# schematic1.net
KiCad netlist of a schematic drawn in EAGLE
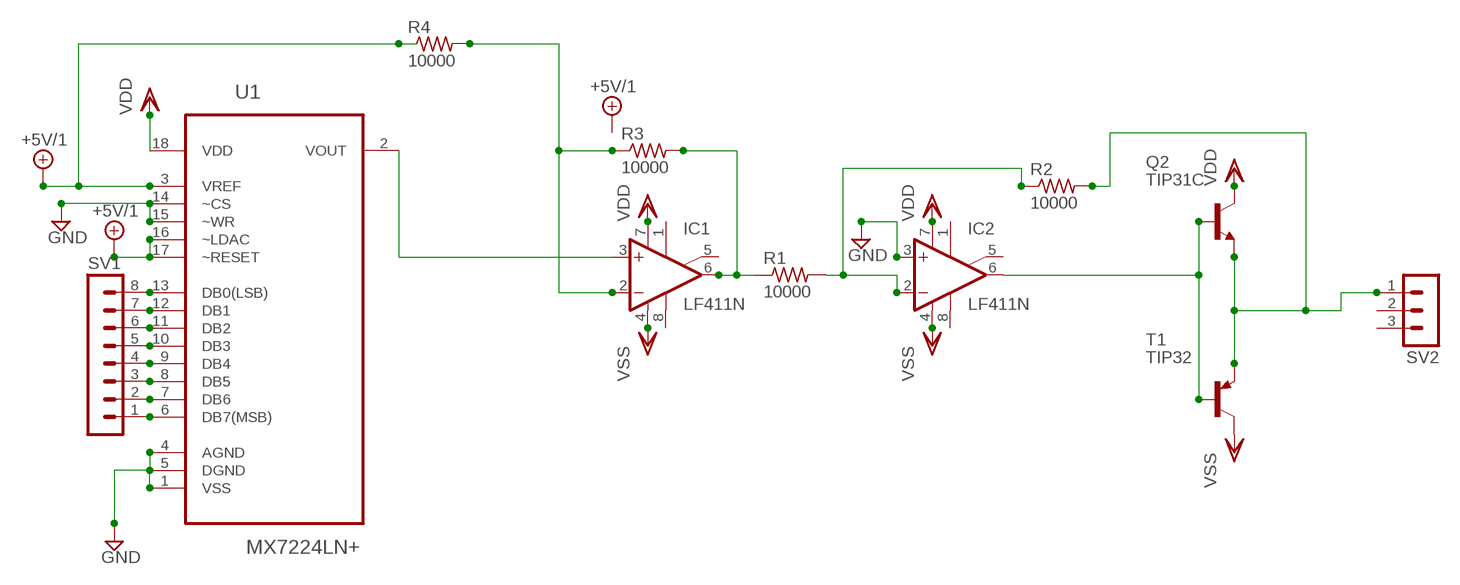
[diagram p0: schematic, sheet 1]

(export (version "E")
  (design (tool "Eeschema 10.0.6"))
  (components
    (comp (ref "IC1")
      (value "LF411N")
      (footprint "eagle-import:DIL08")
      (libsource (lib "eagle-import") (part "LF411N"))
    )
    (comp (ref "IC2")
      (value "LF411N")
      (footprint "eagle-import:DIL08")
      (libsource (lib "eagle-import") (part "LF411N"))
    )
    (comp (ref "Q2")
      (value "TIP31C")
      (footprint "eagle-import:TO220")
      (libsource (lib "eagle-import") (part "TIP31C"))
    )
    (comp (ref "R1")
      (value "10000")
      (footprint "eagle-import:0204_7")
      (libsource (lib "eagle-import") (part "R-US_0204/7"))
    )
    (comp (ref "R2")
      (value "10000")
      (footprint "eagle-import:0204_7")
      (libsource (lib "eagle-import") (part "R-US_0204/7"))
    )
    (comp (ref "R3")
      (value "10000")
      (footprint "eagle-import:0204_7")
      (libsource (lib "eagle-import") (part "R-US_0204/7"))
    )
    (comp (ref "R4")
      (value "10000")
      (footprint "eagle-import:0204_7")
      (fields (field (name "RES") "10000"))
      (libsource (lib "eagle-import") (part "R-US_0204/7"))
    )
    (comp (ref "SV1")
      (value "MA08-1W")
      (footprint "eagle-import:MA08-1W")
      (libsource (lib "eagle-import") (part "MA08-1W"))
    )
    (comp (ref "SV2")
      (value "MA03-1")
      (footprint "eagle-import:MA03-1")
      (libsource (lib "eagle-import") (part "MA03-1"))
    )
    (comp (ref "T1")
      (value "TIP32")
      (footprint "eagle-import:TO220")
      (libsource (lib "eagle-import") (part "TIP32"))
    )
    (comp (ref "U1")
      (value "MX7224LN+")
      (footprint "eagle-import:DIP254P762X457-18")
      (libsource (lib "eagle-import") (part "MX7224LN+"))
    )
  )
  (nets
    (net (code "1") (name "+5V{slash}1") (class "Default")
      (node (ref "R4") (pin "1") (pinfunction "1_1") (pintype "passive"))
      (node (ref "U1") (pin "16") (pinfunction "~{LDAC}_16") (pintype "input"))
      (node (ref "U1") (pin "17") (pinfunction "~{RESET}_17") (pintype "input"))
      (node (ref "U1") (pin "3") (pinfunction "VREF_3") (pintype "passive"))
    )
    (net (code "2") (name "GND") (class "Default")
      (node (ref "IC2") (pin "3") (pinfunction "+IN_3") (pintype "input"))
      (node (ref "U1") (pin "1") (pinfunction "VSS_1") (pintype "power_in"))
      (node (ref "U1") (pin "14") (pinfunction "~{CS}_14") (pintype "input"))
      (node (ref "U1") (pin "15") (pinfunction "~{WR}_15") (pintype "input"))
      (node (ref "U1") (pin "4") (pinfunction "AGND_4") (pintype "passive"))
      (node (ref "U1") (pin "5") (pinfunction "DGND_5") (pintype "passive"))
    )
    (net (code "3") (name "Net-(IC1-+IN)") (class "Default")
      (node (ref "IC1") (pin "3") (pinfunction "+IN_3") (pintype "input"))
      (node (ref "U1") (pin "2") (pinfunction "VOUT_2") (pintype "output"))
    )
    (net (code "4") (name "Net-(IC1--IN)") (class "Default")
      (node (ref "IC1") (pin "2") (pinfunction "-IN_2") (pintype "input"))
      (node (ref "R3") (pin "1") (pinfunction "1_1") (pintype "passive"))
      (node (ref "R4") (pin "2") (pinfunction "2_2") (pintype "passive"))
    )
    (net (code "5") (name "Net-(IC1-OUT)") (class "Default")
      (node (ref "IC1") (pin "6") (pinfunction "OUT_6") (pintype "output"))
      (node (ref "R1") (pin "1") (pinfunction "1_1") (pintype "passive"))
      (node (ref "R3") (pin "2") (pinfunction "2_2") (pintype "passive"))
    )
    (net (code "6") (name "Net-(IC2--IN)") (class "Default")
      (node (ref "IC2") (pin "2") (pinfunction "-IN_2") (pintype "input"))
      (node (ref "R1") (pin "2") (pinfunction "2_2") (pintype "passive"))
      (node (ref "R2") (pin "1") (pinfunction "1_1") (pintype "passive"))
    )
    (net (code "7") (name "Net-(IC2-OUT)") (class "Default")
      (node (ref "IC2") (pin "6") (pinfunction "OUT_6") (pintype "output"))
      (node (ref "Q2") (pin "1") (pinfunction "B_1") (pintype "passive"))
      (node (ref "T1") (pin "1") (pinfunction "B_1") (pintype "passive"))
    )
    (net (code "8") (name "Net-(Q2-E)") (class "Default")
      (node (ref "Q2") (pin "3") (pinfunction "E_3") (pintype "passive"))
      (node (ref "R2") (pin "2") (pinfunction "2_2") (pintype "passive"))
      (node (ref "SV2") (pin "1") (pinfunction "1_1") (pintype "passive"))
      (node (ref "T1") (pin "3") (pinfunction "E_3") (pintype "passive"))
    )
    (net (code "9") (name "Net-(U1-DB0(LSB))") (class "Default")
      (node (ref "SV1") (pin "8") (pinfunction "8_8") (pintype "passive"))
      (node (ref "U1") (pin "13") (pinfunction "DB0(LSB)_13") (pintype "input"))
    )
    (net (code "10") (name "Net-(U1-DB1)") (class "Default")
      (node (ref "SV1") (pin "7") (pinfunction "7_7") (pintype "passive"))
      (node (ref "U1") (pin "12") (pinfunction "DB1_12") (pintype "input"))
    )
    (net (code "11") (name "Net-(U1-DB2)") (class "Default")
      (node (ref "SV1") (pin "6") (pinfunction "6_6") (pintype "passive"))
      (node (ref "U1") (pin "11") (pinfunction "DB2_11") (pintype "input"))
    )
    (net (code "12") (name "Net-(U1-DB3)") (class "Default")
      (node (ref "SV1") (pin "5") (pinfunction "5_5") (pintype "passive"))
      (node (ref "U1") (pin "10") (pinfunction "DB3_10") (pintype "input"))
    )
    (net (code "13") (name "Net-(U1-DB4)") (class "Default")
      (node (ref "SV1") (pin "4") (pinfunction "4_4") (pintype "passive"))
      (node (ref "U1") (pin "9") (pinfunction "DB4_9") (pintype "input"))
    )
    (net (code "14") (name "Net-(U1-DB5)") (class "Default")
      (node (ref "SV1") (pin "3") (pinfunction "3_3") (pintype "passive"))
      (node (ref "U1") (pin "8") (pinfunction "DB5_8") (pintype "input"))
    )
    (net (code "15") (name "Net-(U1-DB6)") (class "Default")
      (node (ref "SV1") (pin "2") (pinfunction "2_2") (pintype "passive"))
      (node (ref "U1") (pin "7") (pinfunction "DB6_7") (pintype "input"))
    )
    (net (code "16") (name "Net-(U1-DB7(MSB))") (class "Default")
      (node (ref "SV1") (pin "1") (pinfunction "1_1") (pintype "passive"))
      (node (ref "U1") (pin "6") (pinfunction "DB7(MSB)_6") (pintype "input"))
    )
    (net (code "17") (name "VDD") (class "Default")
      (node (ref "IC1") (pin "7") (pinfunction "V+_7") (pintype "power_in"))
      (node (ref "IC2") (pin "7") (pinfunction "V+_7") (pintype "power_in"))
      (node (ref "Q2") (pin "2") (pinfunction "C_2") (pintype "passive"))
      (node (ref "U1") (pin "18") (pinfunction "VDD_18") (pintype "power_in"))
    )
    (net (code "18") (name "VSS") (class "Default")
      (node (ref "IC1") (pin "4") (pinfunction "V-_4") (pintype "power_in"))
      (node (ref "IC2") (pin "4") (pinfunction "V-_4") (pintype "power_in"))
      (node (ref "T1") (pin "2") (pinfunction "C_2") (pintype "passive"))
    )
    (net (code "19") (name "unconnected-(IC1-ON1-Pad1)") (class "Default")
      (node (ref "IC1") (pin "1") (pinfunction "ON1_1") (pintype "passive"))
    )
    (net (code "20") (name "unconnected-(IC1-ON2-Pad5)") (class "Default")
      (node (ref "IC1") (pin "5") (pinfunction "ON2_5") (pintype "passive"))
    )
    (net (code "21") (name "unconnected-(IC1-OPT-Pad8)") (class "Default")
      (node (ref "IC1") (pin "8") (pinfunction "OPT_8") (pintype "passive"))
    )
    (net (code "22") (name "unconnected-(IC2-ON1-Pad1)") (class "Default")
      (node (ref "IC2") (pin "1") (pinfunction "ON1_1") (pintype "passive"))
    )
    (net (code "23") (name "unconnected-(IC2-ON2-Pad5)") (class "Default")
      (node (ref "IC2") (pin "5") (pinfunction "ON2_5") (pintype "passive"))
    )
    (net (code "24") (name "unconnected-(IC2-OPT-Pad8)") (class "Default")
      (node (ref "IC2") (pin "8") (pinfunction "OPT_8") (pintype "passive"))
    )
    (net (code "25") (name "unconnected-(SV2-Pad2)") (class "Default")
      (node (ref "SV2") (pin "2") (pinfunction "2_2") (pintype "passive"))
    )
    (net (code "26") (name "unconnected-(SV2-Pad3)") (class "Default")
      (node (ref "SV2") (pin "3") (pinfunction "3_3") (pintype "passive"))
    )
  )
)
